# HallSensor.net
KiCad netlist of a schematic drawn in Altium Designer
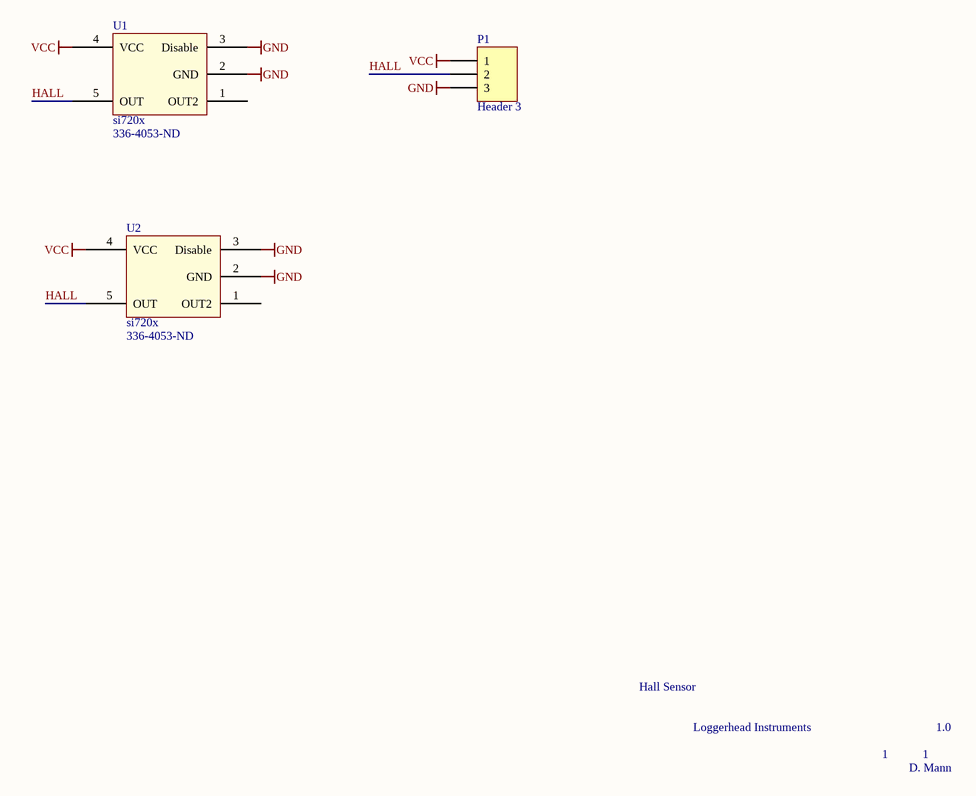
[diagram p0: HallSensor.SchDoc]

(export (version "E")
  (design (tool "Eeschema 10.0.6"))
  (components
    (comp (ref "P1")
      (value "Header 3")
      (footprint "HDR1X3")
      (description "Header, 3-Pin")
      (fields (field (name "PUBLISHER") "Altium Limited"))
      (libsource (lib "Miscellaneous Connectors") (part "Header 3"))
    )
    (comp (ref "U1")
      (value "si720x")
      (footprint "Hall_si720x")
      (description "Hall Sensor")
      (fields (field (name "SUPPLIER PART NUMBER 1") "336-4053-ND"))
      (libsource (lib "Loggerhead") (part "Hall_si720x"))
    )
    (comp (ref "U2")
      (value "si720x")
      (footprint "Hall_si720x")
      (description "Hall Sensor")
      (fields (field (name "SUPPLIER PART NUMBER 1") "336-4053-ND"))
      (libsource (lib "Loggerhead") (part "Hall_si720x"))
    )
  )
  (nets
    (net (code "1") (name "/HALL") (class "Default")
      (node (ref "P1") (pin "2") (pinfunction "2_2") (pintype "passive"))
      (node (ref "U1") (pin "5") (pinfunction "OUT_5") (pintype "passive"))
      (node (ref "U2") (pin "5") (pinfunction "OUT_5") (pintype "passive"))
    )
    (net (code "2") (name "GND") (class "Default")
      (node (ref "P1") (pin "3") (pinfunction "3_3") (pintype "passive"))
      (node (ref "U1") (pin "2") (pinfunction "GND_2") (pintype "passive"))
      (node (ref "U1") (pin "3") (pinfunction "Disable_3") (pintype "passive"))
      (node (ref "U2") (pin "2") (pinfunction "GND_2") (pintype "passive"))
      (node (ref "U2") (pin "3") (pinfunction "Disable_3") (pintype "passive"))
    )
    (net (code "3") (name "VCC") (class "Default")
      (node (ref "P1") (pin "1") (pinfunction "1_1") (pintype "passive"))
      (node (ref "U1") (pin "4") (pinfunction "VCC_4") (pintype "passive"))
      (node (ref "U2") (pin "4") (pinfunction "VCC_4") (pintype "passive"))
    )
    (net (code "4") (name "unconnected-(U1-OUT2-Pad1)") (class "Default")
      (node (ref "U1") (pin "1") (pinfunction "OUT2_1") (pintype "passive"))
    )
    (net (code "5") (name "unconnected-(U2-OUT2-Pad1)") (class "Default")
      (node (ref "U2") (pin "1") (pinfunction "OUT2_1") (pintype "passive"))
    )
  )
)
